# 9_VO_Interface_1.net
KiCad netlist of a schematic drawn in Altium Designer
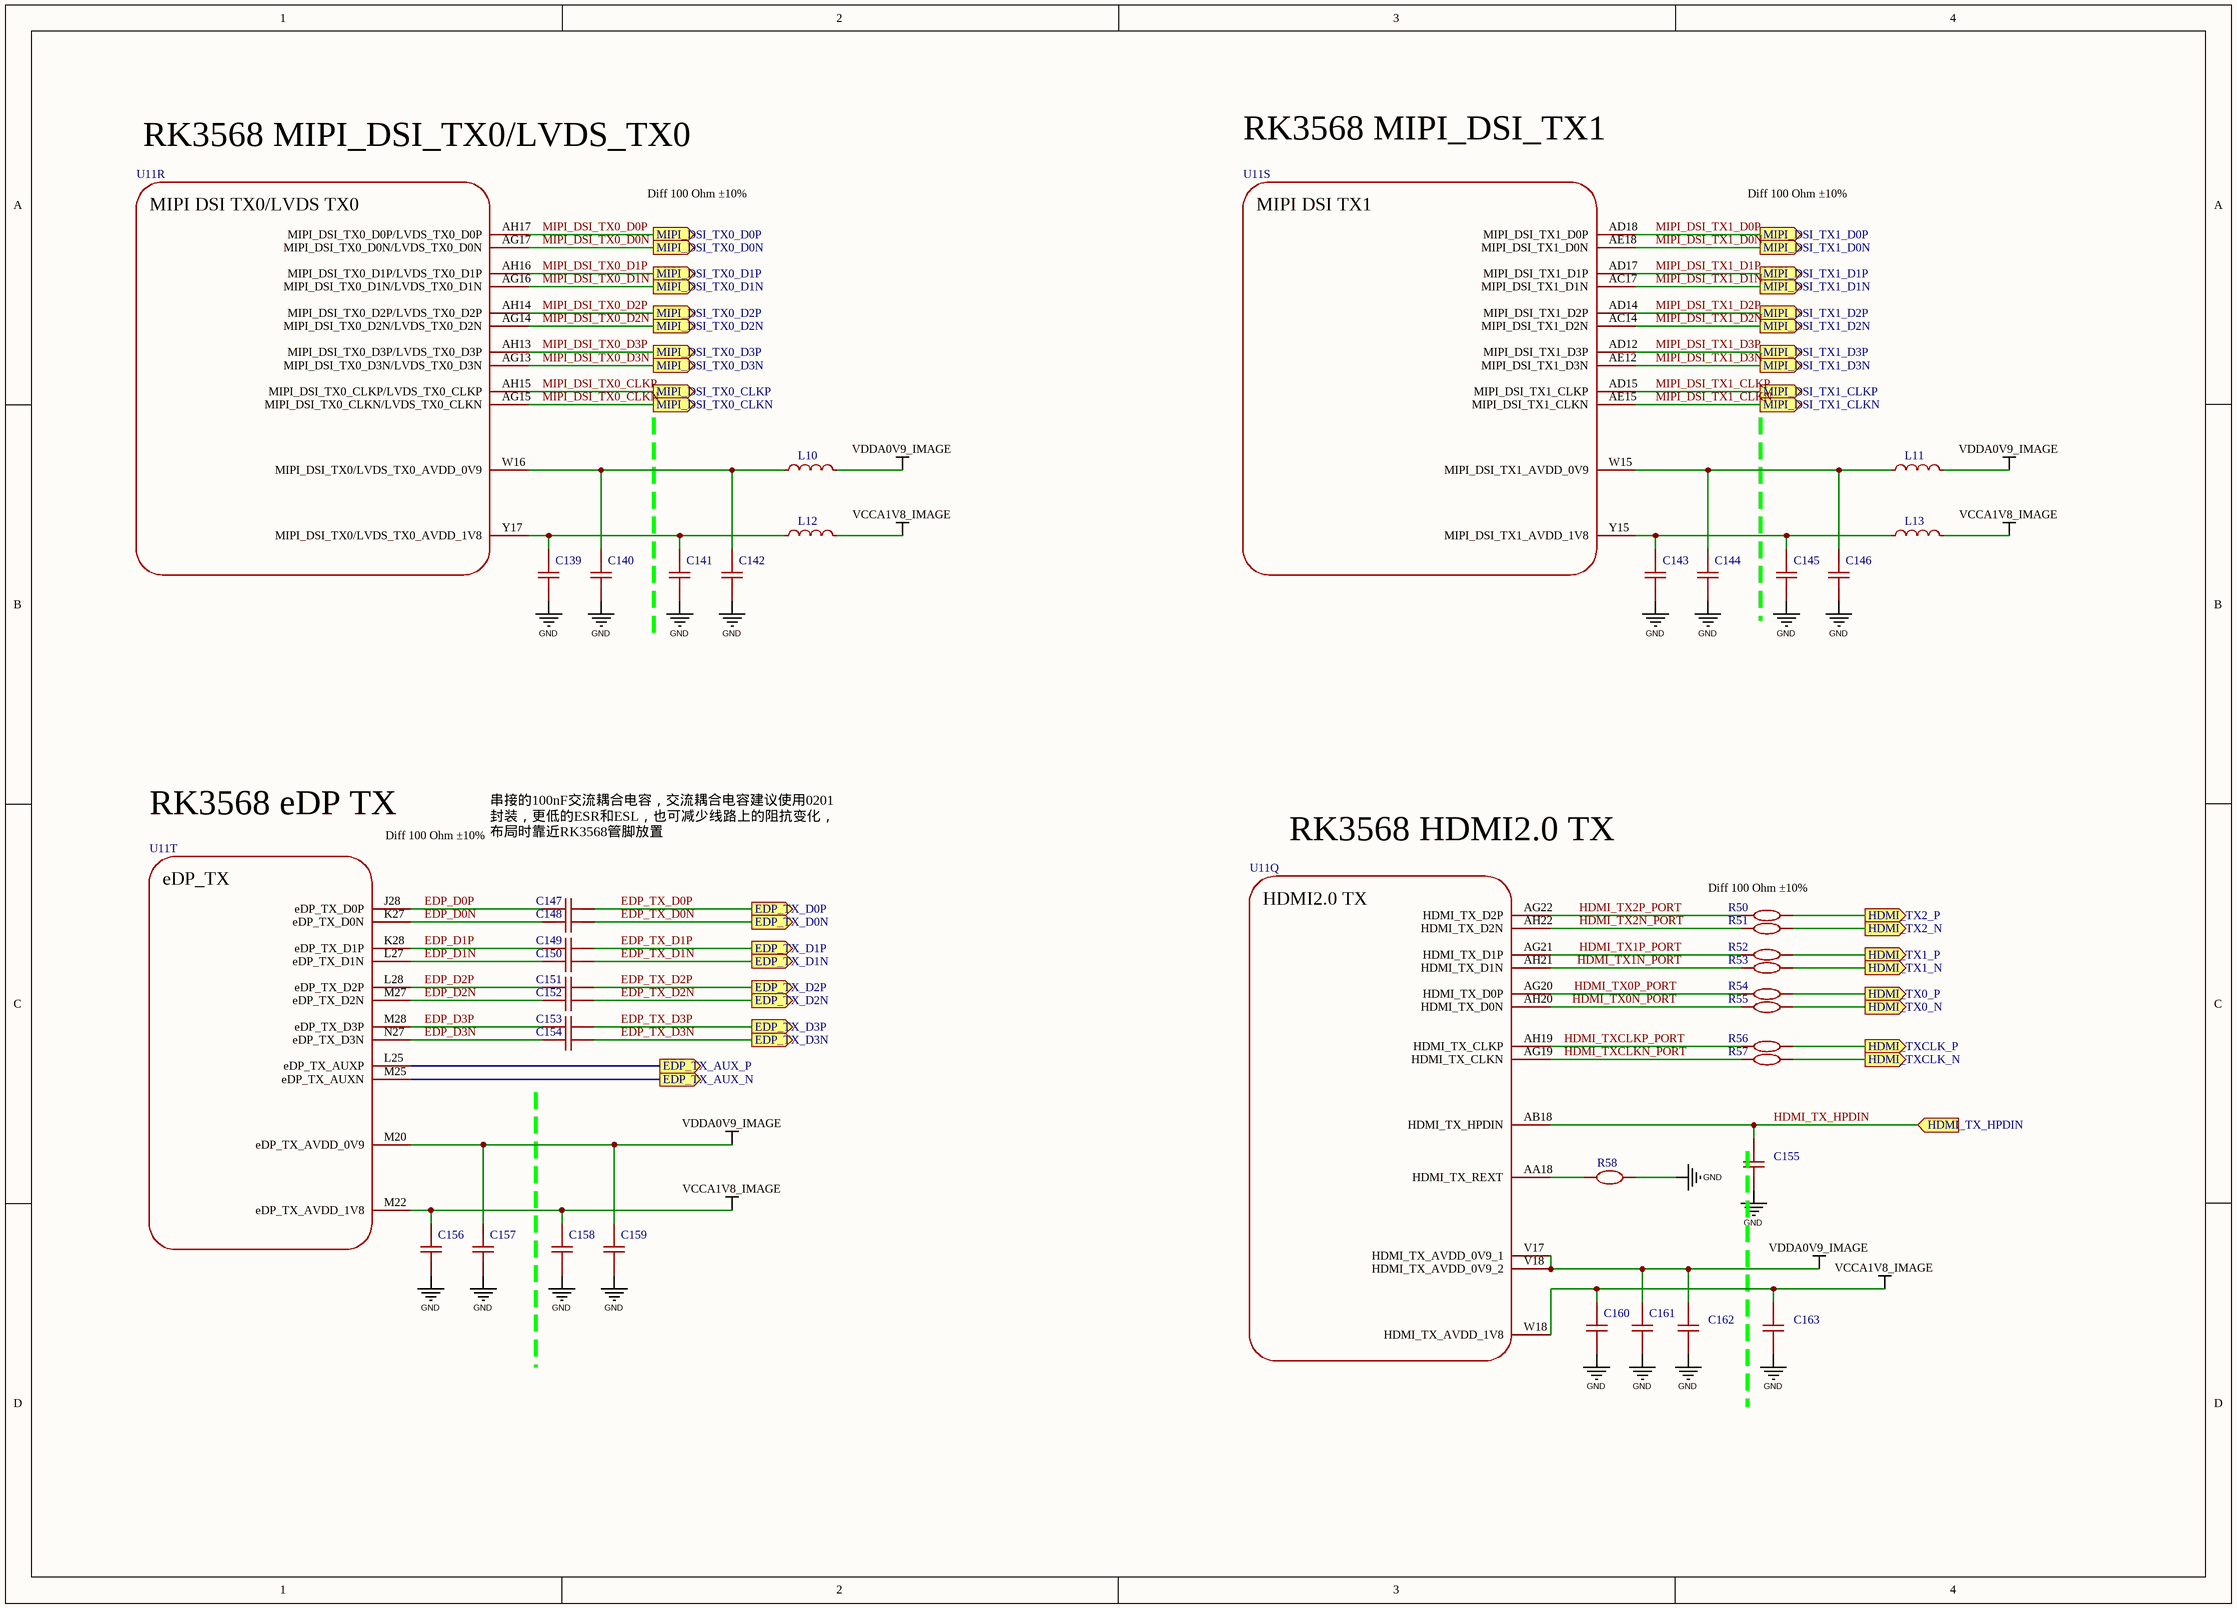
[diagram p0: 9_VO Interface_1.schdoc]

(export (version "E")
  (design (tool "Eeschema 10.0.6"))
  (components
    (comp (ref "C139")
      (value "100nF")
      (footprint "C0201")
      (description "容值:100nF;精度:±10%;额定电压:16V;材质(温度系数):X5R;")
      (fields
        (field (name "MANUFACTURER") "SAMSUNG(三星)")
        (field (name "MANUFACTURER PART") "CL03A104KO3NNNC")
      )
      (libsource (lib "altium-import") (part "root_0_CL03A104KO3NNNC_"))
    )
    (comp (ref "C140")
      (value "100nF")
      (footprint "C0201")
      (description "容值:100nF;精度:±10%;额定电压:16V;材质(温度系数):X5R;")
      (fields
        (field (name "MANUFACTURER") "SAMSUNG(三星)")
        (field (name "MANUFACTURER PART") "CL03A104KO3NNNC")
      )
      (libsource (lib "altium-import") (part "root_0_CL03A104KO3NNNC_"))
    )
    (comp (ref "C141")
      (value "1uF")
      (footprint "C0402")
      (description "容值:1uF;精度:±10%;额定电压:25V;材质(温度系数):X5R;")
      (fields
        (field (name "MANUFACTURER") "SAMSUNG(三星)")
        (field (name "MANUFACTURER PART") "CL05A105KA5NQNC")
      )
      (libsource (lib "altium-import") (part "root_1_CL05A105KA5NQNC_"))
    )
    (comp (ref "C142")
      (value "1uF")
      (footprint "C0402")
      (description "容值:1uF;精度:±10%;额定电压:25V;材质(温度系数):X5R;")
      (fields
        (field (name "MANUFACTURER") "SAMSUNG(三星)")
        (field (name "MANUFACTURER PART") "CL05A105KA5NQNC")
      )
      (libsource (lib "altium-import") (part "root_1_CL05A105KA5NQNC_"))
    )
    (comp (ref "C143")
      (value "100nF")
      (footprint "C0201")
      (description "容值:100nF;精度:±10%;额定电压:16V;材质(温度系数):X5R;")
      (fields
        (field (name "MANUFACTURER") "SAMSUNG(三星)")
        (field (name "MANUFACTURER PART") "CL03A104KO3NNNC")
      )
      (libsource (lib "altium-import") (part "root_0_CL03A104KO3NNNC_"))
    )
    (comp (ref "C144")
      (value "100nF")
      (footprint "C0201")
      (description "容值:100nF;精度:±10%;额定电压:16V;材质(温度系数):X5R;")
      (fields
        (field (name "MANUFACTURER") "SAMSUNG(三星)")
        (field (name "MANUFACTURER PART") "CL03A104KO3NNNC")
      )
      (libsource (lib "altium-import") (part "root_0_CL03A104KO3NNNC_"))
    )
    (comp (ref "C145")
      (value "1uF")
      (footprint "C0402")
      (description "容值:1uF;精度:±10%;额定电压:25V;材质(温度系数):X5R;")
      (fields
        (field (name "MANUFACTURER") "SAMSUNG(三星)")
        (field (name "MANUFACTURER PART") "CL05A105KA5NQNC")
      )
      (libsource (lib "altium-import") (part "root_1_CL05A105KA5NQNC_"))
    )
    (comp (ref "C146")
      (value "1uF")
      (footprint "C0402")
      (description "容值:1uF;精度:±10%;额定电压:25V;材质(温度系数):X5R;")
      (fields
        (field (name "MANUFACTURER") "SAMSUNG(三星)")
        (field (name "MANUFACTURER PART") "CL05A105KA5NQNC")
      )
      (libsource (lib "altium-import") (part "root_1_CL05A105KA5NQNC_"))
    )
    (comp (ref "C147")
      (value "100nF")
      (footprint "C0201")
      (description "容值:100nF;精度:±10%;额定电压:16V;材质(温度系数):X5R;")
      (fields
        (field (name "MANUFACTURER") "SAMSUNG(三星)")
        (field (name "MANUFACTURER PART") "CL03A104KO3NNNC")
      )
      (libsource (lib "altium-import") (part "root_1_CL03A104KO3NNNC_"))
    )
    (comp (ref "C148")
      (value "100nF")
      (footprint "C0201")
      (description "容值:100nF;精度:±10%;额定电压:16V;材质(温度系数):X5R;")
      (fields
        (field (name "MANUFACTURER") "SAMSUNG(三星)")
        (field (name "MANUFACTURER PART") "CL03A104KO3NNNC")
      )
      (libsource (lib "altium-import") (part "root_3_CL03A104KO3NNNC_"))
    )
    (comp (ref "C149")
      (value "100nF")
      (footprint "C0201")
      (description "容值:100nF;精度:±10%;额定电压:16V;材质(温度系数):X5R;")
      (fields
        (field (name "MANUFACTURER") "SAMSUNG(三星)")
        (field (name "MANUFACTURER PART") "CL03A104KO3NNNC")
      )
      (libsource (lib "altium-import") (part "root_1_CL03A104KO3NNNC_"))
    )
    (comp (ref "C150")
      (value "100nF")
      (footprint "C0201")
      (description "容值:100nF;精度:±10%;额定电压:16V;材质(温度系数):X5R;")
      (fields
        (field (name "MANUFACTURER") "SAMSUNG(三星)")
        (field (name "MANUFACTURER PART") "CL03A104KO3NNNC")
      )
      (libsource (lib "altium-import") (part "root_3_CL03A104KO3NNNC_"))
    )
    (comp (ref "C151")
      (value "100nF")
      (footprint "C0201")
      (description "容值:100nF;精度:±10%;额定电压:16V;材质(温度系数):X5R;")
      (fields
        (field (name "MANUFACTURER") "SAMSUNG(三星)")
        (field (name "MANUFACTURER PART") "CL03A104KO3NNNC")
      )
      (libsource (lib "altium-import") (part "root_1_CL03A104KO3NNNC_"))
    )
    (comp (ref "C152")
      (value "100nF")
      (footprint "C0201")
      (description "容值:100nF;精度:±10%;额定电压:16V;材质(温度系数):X5R;")
      (fields
        (field (name "MANUFACTURER") "SAMSUNG(三星)")
        (field (name "MANUFACTURER PART") "CL03A104KO3NNNC")
      )
      (libsource (lib "altium-import") (part "root_3_CL03A104KO3NNNC_"))
    )
    (comp (ref "C153")
      (value "100nF")
      (footprint "C0201")
      (description "容值:100nF;精度:±10%;额定电压:16V;材质(温度系数):X5R;")
      (fields
        (field (name "MANUFACTURER") "SAMSUNG(三星)")
        (field (name "MANUFACTURER PART") "CL03A104KO3NNNC")
      )
      (libsource (lib "altium-import") (part "root_1_CL03A104KO3NNNC_"))
    )
    (comp (ref "C154")
      (value "100nF")
      (footprint "C0201")
      (description "容值:100nF;精度:±10%;额定电压:16V;材质(温度系数):X5R;")
      (fields
        (field (name "MANUFACTURER") "SAMSUNG(三星)")
        (field (name "MANUFACTURER PART") "CL03A104KO3NNNC")
      )
      (libsource (lib "altium-import") (part "root_3_CL03A104KO3NNNC_"))
    )
    (comp (ref "C155")
      (value "100nF")
      (footprint "C0402")
      (description "容值:100nF;精度:±10%;额定电压:50V;材质(温度系数):X7R;")
      (fields
        (field (name "MANUFACTURER") "SAMSUNG(三星)")
        (field (name "MANUFACTURER PART") "CL05B104KB54PNC")
      )
      (libsource (lib "altium-import") (part "root_1_CL05B104KB54PNC_"))
    )
    (comp (ref "C156")
      (value "100nF")
      (footprint "C0201")
      (description "容值:100nF;精度:±10%;额定电压:16V;材质(温度系数):X5R;")
      (fields
        (field (name "MANUFACTURER") "SAMSUNG(三星)")
        (field (name "MANUFACTURER PART") "CL03A104KO3NNNC")
      )
      (libsource (lib "altium-import") (part "root_0_CL03A104KO3NNNC_"))
    )
    (comp (ref "C157")
      (value "100nF")
      (footprint "C0201")
      (description "容值:100nF;精度:±10%;额定电压:16V;材质(温度系数):X5R;")
      (fields
        (field (name "MANUFACTURER") "SAMSUNG(三星)")
        (field (name "MANUFACTURER PART") "CL03A104KO3NNNC")
      )
      (libsource (lib "altium-import") (part "root_0_CL03A104KO3NNNC_"))
    )
    (comp (ref "C158")
      (value "1uF")
      (footprint "C0402")
      (description "容值:1uF;精度:±10%;额定电压:25V;材质(温度系数):X5R;")
      (fields
        (field (name "MANUFACTURER") "SAMSUNG(三星)")
        (field (name "MANUFACTURER PART") "CL05A105KA5NQNC")
      )
      (libsource (lib "altium-import") (part "root_1_CL05A105KA5NQNC_"))
    )
    (comp (ref "C159")
      (value "1uF")
      (footprint "C0402")
      (description "容值:1uF;精度:±10%;额定电压:25V;材质(温度系数):X5R;")
      (fields
        (field (name "MANUFACTURER") "SAMSUNG(三星)")
        (field (name "MANUFACTURER PART") "CL05A105KA5NQNC")
      )
      (libsource (lib "altium-import") (part "root_1_CL05A105KA5NQNC_"))
    )
    (comp (ref "C160")
      (value "100nF")
      (footprint "C0201")
      (description "容值:100nF;精度:±10%;额定电压:16V;材质(温度系数):X5R;")
      (fields
        (field (name "MANUFACTURER") "SAMSUNG(三星)")
        (field (name "MANUFACTURER PART") "CL03A104KO3NNNC")
      )
      (libsource (lib "altium-import") (part "root_0_CL03A104KO3NNNC_"))
    )
    (comp (ref "C161")
      (value "100nF")
      (footprint "C0201")
      (description "容值:100nF;精度:±10%;额定电压:16V;材质(温度系数):X5R;")
      (fields
        (field (name "MANUFACTURER") "SAMSUNG(三星)")
        (field (name "MANUFACTURER PART") "CL03A104KO3NNNC")
      )
      (libsource (lib "altium-import") (part "root_0_CL03A104KO3NNNC_"))
    )
    (comp (ref "C162")
      (value "4.7uF")
      (footprint "C0201")
      (description "容值:4.7uF;精度:±20%;额定电压:6.3V;材质(温度系数):X5R;")
      (fields
        (field (name "MANUFACTURER") "muRata(村田)")
        (field (name "MANUFACTURER PART") "GRM035R60J475ME15D")
      )
      (libsource (lib "altium-import") (part "root_2_GRM035R60J475ME15D_"))
    )
    (comp (ref "C163")
      (value "4.7uF")
      (footprint "C0201")
      (description "容值:4.7uF;精度:±20%;额定电压:6.3V;材质(温度系数):X5R;")
      (fields
        (field (name "MANUFACTURER") "muRata(村田)")
        (field (name "MANUFACTURER PART") "GRM035R60J475ME15D")
      )
      (libsource (lib "altium-import") (part "root_2_GRM035R60J475ME15D_"))
    )
    (comp (ref "L10")
      (value "120R 100MHz")
      (footprint "L0603")
      (description "标称阻抗@测试频率:120Ω@100MHz;误差:±25%;直流电阻(RDC):50mΩ;")
      (fields (field (name "MANUFACTURER") "muRata(村田)") (field (name "TOLERANCE") "±25%"))
      (libsource (lib "altium-import") (part "root_0_BLM18PG121SN1D_"))
    )
    (comp (ref "L11")
      (value "120R 100MHz")
      (footprint "L0603")
      (description "标称阻抗@测试频率:120Ω@100MHz;误差:±25%;直流电阻(RDC):50mΩ;")
      (fields (field (name "MANUFACTURER") "muRata(村田)") (field (name "TOLERANCE") "±25%"))
      (libsource (lib "altium-import") (part "root_0_BLM18PG121SN1D_"))
    )
    (comp (ref "L12")
      (value "120R 100MHz")
      (footprint "L0603")
      (description "标称阻抗@测试频率:120Ω@100MHz;误差:±25%;直流电阻(RDC):50mΩ;")
      (fields (field (name "MANUFACTURER") "muRata(村田)") (field (name "TOLERANCE") "±25%"))
      (libsource (lib "altium-import") (part "root_0_BLM18PG121SN1D_"))
    )
    (comp (ref "L13")
      (value "120R 100MHz")
      (footprint "L0603")
      (description "标称阻抗@测试频率:120Ω@100MHz;误差:±25%;直流电阻(RDC):50mΩ;")
      (fields (field (name "MANUFACTURER") "muRata(村田)") (field (name "TOLERANCE") "±25%"))
      (libsource (lib "altium-import") (part "root_0_BLM18PG121SN1D_"))
    )
    (comp (ref "R50")
      (value "2.2Ω")
      (footprint "R0201")
      (description "电阻类型:厚膜电阻;阻值:2.2Ω;精度:±5%;功率:50mW;最大工作电压:25V;温度系数:±400ppm/℃;")
      (fields
        (field (name "MANUFACTURER") "UNI-ROYAL(厚声)")
        (field (name "MANUFACTURER PART") "0201WMJ022JTEE")
      )
      (libsource (lib "altium-import") (part "root_0_0201WMJ022JTEE_"))
    )
    (comp (ref "R51")
      (value "2.2Ω")
      (footprint "R0201")
      (description "电阻类型:厚膜电阻;阻值:2.2Ω;精度:±5%;功率:50mW;最大工作电压:25V;温度系数:±400ppm/℃;")
      (fields
        (field (name "MANUFACTURER") "UNI-ROYAL(厚声)")
        (field (name "MANUFACTURER PART") "0201WMJ022JTEE")
      )
      (libsource (lib "altium-import") (part "root_0_0201WMJ022JTEE_"))
    )
    (comp (ref "R52")
      (value "2.2Ω")
      (footprint "R0201")
      (description "电阻类型:厚膜电阻;阻值:2.2Ω;精度:±5%;功率:50mW;最大工作电压:25V;温度系数:±400ppm/℃;")
      (fields
        (field (name "MANUFACTURER") "UNI-ROYAL(厚声)")
        (field (name "MANUFACTURER PART") "0201WMJ022JTEE")
      )
      (libsource (lib "altium-import") (part "root_0_0201WMJ022JTEE_"))
    )
    (comp (ref "R53")
      (value "2.2Ω")
      (footprint "R0201")
      (description "电阻类型:厚膜电阻;阻值:2.2Ω;精度:±5%;功率:50mW;最大工作电压:25V;温度系数:±400ppm/℃;")
      (fields
        (field (name "MANUFACTURER") "UNI-ROYAL(厚声)")
        (field (name "MANUFACTURER PART") "0201WMJ022JTEE")
      )
      (libsource (lib "altium-import") (part "root_0_0201WMJ022JTEE_"))
    )
    (comp (ref "R54")
      (value "2.2Ω")
      (footprint "R0201")
      (description "电阻类型:厚膜电阻;阻值:2.2Ω;精度:±5%;功率:50mW;最大工作电压:25V;温度系数:±400ppm/℃;")
      (fields
        (field (name "MANUFACTURER") "UNI-ROYAL(厚声)")
        (field (name "MANUFACTURER PART") "0201WMJ022JTEE")
      )
      (libsource (lib "altium-import") (part "root_0_0201WMJ022JTEE_"))
    )
    (comp (ref "R55")
      (value "2.2Ω")
      (footprint "R0201")
      (description "电阻类型:厚膜电阻;阻值:2.2Ω;精度:±5%;功率:50mW;最大工作电压:25V;温度系数:±400ppm/℃;")
      (fields
        (field (name "MANUFACTURER") "UNI-ROYAL(厚声)")
        (field (name "MANUFACTURER PART") "0201WMJ022JTEE")
      )
      (libsource (lib "altium-import") (part "root_0_0201WMJ022JTEE_"))
    )
    (comp (ref "R56")
      (value "2.2Ω")
      (footprint "R0201")
      (description "电阻类型:厚膜电阻;阻值:2.2Ω;精度:±5%;功率:50mW;最大工作电压:25V;温度系数:±400ppm/℃;")
      (fields
        (field (name "MANUFACTURER") "UNI-ROYAL(厚声)")
        (field (name "MANUFACTURER PART") "0201WMJ022JTEE")
      )
      (libsource (lib "altium-import") (part "root_0_0201WMJ022JTEE_"))
    )
    (comp (ref "R57")
      (value "2.2Ω")
      (footprint "R0201")
      (description "电阻类型:厚膜电阻;阻值:2.2Ω;精度:±5%;功率:50mW;最大工作电压:25V;温度系数:±400ppm/℃;")
      (fields
        (field (name "MANUFACTURER") "UNI-ROYAL(厚声)")
        (field (name "MANUFACTURER PART") "0201WMJ022JTEE")
      )
      (libsource (lib "altium-import") (part "root_0_0201WMJ022JTEE_"))
    )
    (comp (ref "R58")
      (value "1.62kΩ")
      (footprint "R0201")
      (description "电阻类型:厚膜电阻;阻值:1.62kΩ;精度:±1%;功率:50mW;最大工作电压:25V;温度系数:±200ppm/℃;")
      (fields
        (field (name "MANUFACTURER") "UNI-ROYAL(厚声)")
        (field (name "MANUFACTURER PART") "0201WMF1621TEE")
      )
      (libsource (lib "altium-import") (part "root_0_0201WMF1621TEE_"))
    )
    (comp (ref "U11")
      (value "SOC_RK3568")
      (footprint "RK3568")
      (fields (field (name "MANUFACTURER") "Rockchip (瑞芯微)") (field (name "CREATED BY") "JJJ"))
      (libsource (lib "altium-import") (part "root_0_SOC_RK3568_"))
    )
  )
  (nets
    (net (code "1") (name "/EDP_D0N") (class "Default")
      (node (ref "C148") (pin "1") (pinfunction "1_1") (pintype "passive"))
      (node (ref "U11") (pin "K27") (pinfunction "eDP_TX_D0N_K27") (pintype "passive"))
    )
    (net (code "2") (name "/EDP_D0P") (class "Default")
      (node (ref "C147") (pin "2") (pinfunction "2_2") (pintype "passive"))
      (node (ref "U11") (pin "J28") (pinfunction "eDP_TX_D0P_J28") (pintype "passive"))
    )
    (net (code "3") (name "/EDP_D1N") (class "Default")
      (node (ref "C150") (pin "1") (pinfunction "1_1") (pintype "passive"))
      (node (ref "U11") (pin "L27") (pinfunction "eDP_TX_D1N_L27") (pintype "passive"))
    )
    (net (code "4") (name "/EDP_D1P") (class "Default")
      (node (ref "C149") (pin "2") (pinfunction "2_2") (pintype "passive"))
      (node (ref "U11") (pin "K28") (pinfunction "eDP_TX_D1P_K28") (pintype "passive"))
    )
    (net (code "5") (name "/EDP_D2N") (class "Default")
      (node (ref "C152") (pin "1") (pinfunction "1_1") (pintype "passive"))
      (node (ref "U11") (pin "M27") (pinfunction "eDP_TX_D2N_M27") (pintype "passive"))
    )
    (net (code "6") (name "/EDP_D2P") (class "Default")
      (node (ref "C151") (pin "2") (pinfunction "2_2") (pintype "passive"))
      (node (ref "U11") (pin "L28") (pinfunction "eDP_TX_D2P_L28") (pintype "passive"))
    )
    (net (code "7") (name "/EDP_D3N") (class "Default")
      (node (ref "C154") (pin "1") (pinfunction "1_1") (pintype "passive"))
      (node (ref "U11") (pin "N27") (pinfunction "eDP_TX_D3N_N27") (pintype "passive"))
    )
    (net (code "8") (name "/EDP_D3P") (class "Default")
      (node (ref "C153") (pin "2") (pinfunction "2_2") (pintype "passive"))
      (node (ref "U11") (pin "M28") (pinfunction "eDP_TX_D3P_M28") (pintype "passive"))
    )
    (net (code "9") (name "/EDP_TX_AUX_N") (class "Default")
      (node (ref "U11") (pin "M25") (pinfunction "eDP_TX_AUXN_M25") (pintype "passive"))
    )
    (net (code "10") (name "/EDP_TX_AUX_P") (class "Default")
      (node (ref "U11") (pin "L25") (pinfunction "eDP_TX_AUXP_L25") (pintype "passive"))
    )
    (net (code "11") (name "/EDP_TX_D0N") (class "Default")
      (node (ref "C148") (pin "2") (pinfunction "2_2") (pintype "passive"))
    )
    (net (code "12") (name "/EDP_TX_D0P") (class "Default")
      (node (ref "C147") (pin "1") (pinfunction "1_1") (pintype "passive"))
    )
    (net (code "13") (name "/EDP_TX_D1N") (class "Default")
      (node (ref "C150") (pin "2") (pinfunction "2_2") (pintype "passive"))
    )
    (net (code "14") (name "/EDP_TX_D1P") (class "Default")
      (node (ref "C149") (pin "1") (pinfunction "1_1") (pintype "passive"))
    )
    (net (code "15") (name "/EDP_TX_D2N") (class "Default")
      (node (ref "C152") (pin "2") (pinfunction "2_2") (pintype "passive"))
    )
    (net (code "16") (name "/EDP_TX_D2P") (class "Default")
      (node (ref "C151") (pin "1") (pinfunction "1_1") (pintype "passive"))
    )
    (net (code "17") (name "/EDP_TX_D3N") (class "Default")
      (node (ref "C154") (pin "2") (pinfunction "2_2") (pintype "passive"))
    )
    (net (code "18") (name "/EDP_TX_D3P") (class "Default")
      (node (ref "C153") (pin "1") (pinfunction "1_1") (pintype "passive"))
    )
    (net (code "19") (name "/HDMI_TX0N_PORT") (class "Default")
      (node (ref "R55") (pin "1") (pinfunction "1_1") (pintype "passive"))
      (node (ref "U11") (pin "AH20") (pinfunction "HDMI_TX_D0N_AH20") (pintype "passive"))
    )
    (net (code "20") (name "/HDMI_TX0P_PORT") (class "Default")
      (node (ref "R54") (pin "1") (pinfunction "1_1") (pintype "passive"))
      (node (ref "U11") (pin "AG20") (pinfunction "HDMI_TX_D0P_AG20") (pintype "passive"))
    )
    (net (code "21") (name "/HDMI_TX0_N") (class "Default")
      (node (ref "R55") (pin "2") (pinfunction "2_2") (pintype "passive"))
    )
    (net (code "22") (name "/HDMI_TX0_P") (class "Default")
      (node (ref "R54") (pin "2") (pinfunction "2_2") (pintype "passive"))
    )
    (net (code "23") (name "/HDMI_TX1N_PORT") (class "Default")
      (node (ref "R53") (pin "1") (pinfunction "1_1") (pintype "passive"))
      (node (ref "U11") (pin "AH21") (pinfunction "HDMI_TX_D1N_AH21") (pintype "passive"))
    )
    (net (code "24") (name "/HDMI_TX1P_PORT") (class "Default")
      (node (ref "R52") (pin "1") (pinfunction "1_1") (pintype "passive"))
      (node (ref "U11") (pin "AG21") (pinfunction "HDMI_TX_D1P_AG21") (pintype "passive"))
    )
    (net (code "25") (name "/HDMI_TX1_N") (class "Default")
      (node (ref "R53") (pin "2") (pinfunction "2_2") (pintype "passive"))
    )
    (net (code "26") (name "/HDMI_TX1_P") (class "Default")
      (node (ref "R52") (pin "2") (pinfunction "2_2") (pintype "passive"))
    )
    (net (code "27") (name "/HDMI_TX2N_PORT") (class "Default")
      (node (ref "R51") (pin "1") (pinfunction "1_1") (pintype "passive"))
      (node (ref "U11") (pin "AH22") (pinfunction "HDMI_TX_D2N_AH22") (pintype "passive"))
    )
    (net (code "28") (name "/HDMI_TX2P_PORT") (class "Default")
      (node (ref "R50") (pin "1") (pinfunction "1_1") (pintype "passive"))
      (node (ref "U11") (pin "AG22") (pinfunction "HDMI_TX_D2P_AG22") (pintype "passive"))
    )
    (net (code "29") (name "/HDMI_TX2_N") (class "Default")
      (node (ref "R51") (pin "2") (pinfunction "2_2") (pintype "passive"))
    )
    (net (code "30") (name "/HDMI_TX2_P") (class "Default")
      (node (ref "R50") (pin "2") (pinfunction "2_2") (pintype "passive"))
    )
    (net (code "31") (name "/HDMI_TXCLKN_PORT") (class "Default")
      (node (ref "R57") (pin "1") (pinfunction "1_1") (pintype "passive"))
      (node (ref "U11") (pin "AG19") (pinfunction "HDMI_TX_CLKN_AG19") (pintype "passive"))
    )
    (net (code "32") (name "/HDMI_TXCLKP_PORT") (class "Default")
      (node (ref "R56") (pin "1") (pinfunction "1_1") (pintype "passive"))
      (node (ref "U11") (pin "AH19") (pinfunction "HDMI_TX_CLKP_AH19") (pintype "passive"))
    )
    (net (code "33") (name "/HDMI_TXCLK_N") (class "Default")
      (node (ref "R57") (pin "2") (pinfunction "2_2") (pintype "passive"))
    )
    (net (code "34") (name "/HDMI_TXCLK_P") (class "Default")
      (node (ref "R56") (pin "2") (pinfunction "2_2") (pintype "passive"))
    )
    (net (code "35") (name "/HDMI_TX_HPDIN") (class "Default")
      (node (ref "C155") (pin "2") (pinfunction "2_2") (pintype "passive"))
      (node (ref "U11") (pin "AB18") (pinfunction "HDMI_TX_HPDIN_AB18") (pintype "passive"))
    )
    (net (code "36") (name "/MIPI_DSI_TX0_CLKN") (class "Default")
      (node (ref "U11") (pin "AG15") (pinfunction "MIPI_DSI_TX0_CLKN/LVDS_TX0_CLKN_AG15") (pintype "passive"))
    )
    (net (code "37") (name "/MIPI_DSI_TX0_CLKP") (class "Default")
      (node (ref "U11") (pin "AH15") (pinfunction "MIPI_DSI_TX0_CLKP/LVDS_TX0_CLKP_AH15") (pintype "passive"))
    )
    (net (code "38") (name "/MIPI_DSI_TX0_D0N") (class "Default")
      (node (ref "U11") (pin "AG17") (pinfunction "MIPI_DSI_TX0_D0N/LVDS_TX0_D0N_AG17") (pintype "passive"))
    )
    (net (code "39") (name "/MIPI_DSI_TX0_D0P") (class "Default")
      (node (ref "U11") (pin "AH17") (pinfunction "MIPI_DSI_TX0_D0P/LVDS_TX0_D0P_AH17") (pintype "passive"))
    )
    (net (code "40") (name "/MIPI_DSI_TX0_D1N") (class "Default")
      (node (ref "U11") (pin "AG16") (pinfunction "MIPI_DSI_TX0_D1N/LVDS_TX0_D1N_AG16") (pintype "passive"))
    )
    (net (code "41") (name "/MIPI_DSI_TX0_D1P") (class "Default")
      (node (ref "U11") (pin "AH16") (pinfunction "MIPI_DSI_TX0_D1P/LVDS_TX0_D1P_AH16") (pintype "passive"))
    )
    (net (code "42") (name "/MIPI_DSI_TX0_D2N") (class "Default")
      (node (ref "U11") (pin "AG14") (pinfunction "MIPI_DSI_TX0_D2N/LVDS_TX0_D2N_AG14") (pintype "passive"))
    )
    (net (code "43") (name "/MIPI_DSI_TX0_D2P") (class "Default")
      (node (ref "U11") (pin "AH14") (pinfunction "MIPI_DSI_TX0_D2P/LVDS_TX0_D2P_AH14") (pintype "passive"))
    )
    (net (code "44") (name "/MIPI_DSI_TX0_D3N") (class "Default")
      (node (ref "U11") (pin "AG13") (pinfunction "MIPI_DSI_TX0_D3N/LVDS_TX0_D3N_AG13") (pintype "passive"))
    )
    (net (code "45") (name "/MIPI_DSI_TX0_D3P") (class "Default")
      (node (ref "U11") (pin "AH13") (pinfunction "MIPI_DSI_TX0_D3P/LVDS_TX0_D3P_AH13") (pintype "passive"))
    )
    (net (code "46") (name "/MIPI_DSI_TX1_CLKN") (class "Default")
      (node (ref "U11") (pin "AE15") (pinfunction "MIPI_DSI_TX1_CLKN_AE15") (pintype "passive"))
    )
    (net (code "47") (name "/MIPI_DSI_TX1_CLKP") (class "Default")
      (node (ref "U11") (pin "AD15") (pinfunction "MIPI_DSI_TX1_CLKP_AD15") (pintype "passive"))
    )
    (net (code "48") (name "/MIPI_DSI_TX1_D0N") (class "Default")
      (node (ref "U11") (pin "AE18") (pinfunction "MIPI_DSI_TX1_D0N_AE18") (pintype "passive"))
    )
    (net (code "49") (name "/MIPI_DSI_TX1_D0P") (class "Default")
      (node (ref "U11") (pin "AD18") (pinfunction "MIPI_DSI_TX1_D0P_AD18") (pintype "passive"))
    )
    (net (code "50") (name "/MIPI_DSI_TX1_D1N") (class "Default")
      (node (ref "U11") (pin "AC17") (pinfunction "MIPI_DSI_TX1_D1N_AC17") (pintype "passive"))
    )
    (net (code "51") (name "/MIPI_DSI_TX1_D1P") (class "Default")
      (node (ref "U11") (pin "AD17") (pinfunction "MIPI_DSI_TX1_D1P_AD17") (pintype "passive"))
    )
    (net (code "52") (name "/MIPI_DSI_TX1_D2N") (class "Default")
      (node (ref "U11") (pin "AC14") (pinfunction "MIPI_DSI_TX1_D2N_AC14") (pintype "passive"))
    )
    (net (code "53") (name "/MIPI_DSI_TX1_D2P") (class "Default")
      (node (ref "U11") (pin "AD14") (pinfunction "MIPI_DSI_TX1_D2P_AD14") (pintype "passive"))
    )
    (net (code "54") (name "/MIPI_DSI_TX1_D3N") (class "Default")
      (node (ref "U11") (pin "AE12") (pinfunction "MIPI_DSI_TX1_D3N_AE12") (pintype "passive"))
    )
    (net (code "55") (name "/MIPI_DSI_TX1_D3P") (class "Default")
      (node (ref "U11") (pin "AD12") (pinfunction "MIPI_DSI_TX1_D3P_AD12") (pintype "passive"))
    )
    (net (code "56") (name "GND") (class "Default")
      (node (ref "C139") (pin "1") (pinfunction "1_1") (pintype "passive"))
      (node (ref "C140") (pin "1") (pinfunction "1_1") (pintype "passive"))
      (node (ref "C141") (pin "1") (pinfunction "1_1") (pintype "passive"))
      (node (ref "C142") (pin "1") (pinfunction "1_1") (pintype "passive"))
      (node (ref "C143") (pin "1") (pinfunction "1_1") (pintype "passive"))
      (node (ref "C144") (pin "1") (pinfunction "1_1") (pintype "passive"))
      (node (ref "C145") (pin "1") (pinfunction "1_1") (pintype "passive"))
      (node (ref "C146") (pin "1") (pinfunction "1_1") (pintype "passive"))
      (node (ref "C155") (pin "1") (pinfunction "1_1") (pintype "passive"))
      (node (ref "C156") (pin "1") (pinfunction "1_1") (pintype "passive"))
      (node (ref "C157") (pin "1") (pinfunction "1_1") (pintype "passive"))
      (node (ref "C158") (pin "1") (pinfunction "1_1") (pintype "passive"))
      (node (ref "C159") (pin "1") (pinfunction "1_1") (pintype "passive"))
      (node (ref "C160") (pin "1") (pinfunction "1_1") (pintype "passive"))
      (node (ref "C161") (pin "1") (pinfunction "1_1") (pintype "passive"))
      (node (ref "C162") (pin "2") (pinfunction "2_2") (pintype "passive"))
      (node (ref "C163") (pin "2") (pinfunction "2_2") (pintype "passive"))
      (node (ref "R58") (pin "2") (pinfunction "2_2") (pintype "passive"))
    )
    (net (code "57") (name "Net-(U11Q-HDMI_TX_REXT)") (class "Default")
      (node (ref "R58") (pin "1") (pinfunction "1_1") (pintype "passive"))
      (node (ref "U11") (pin "AA18") (pinfunction "HDMI_TX_REXT_AA18") (pintype "passive"))
    )
    (net (code "58") (name "Net-(U11R-MIPI_DSI_TX0{slash}LVDS_TX0_AVDD_0V9)") (class "Default")
      (node (ref "C140") (pin "2") (pinfunction "2_2") (pintype "passive"))
      (node (ref "C142") (pin "2") (pinfunction "2_2") (pintype "passive"))
      (node (ref "L10") (pin "1") (pinfunction "1_1") (pintype "passive"))
      (node (ref "U11") (pin "W16") (pinfunction "MIPI_DSI_TX0/LVDS_TX0_AVDD_0V9_W16") (pintype "passive"))
    )
    (net (code "59") (name "Net-(U11R-MIPI_DSI_TX0{slash}LVDS_TX0_AVDD_1V8)") (class "Default")
      (node (ref "C139") (pin "2") (pinfunction "2_2") (pintype "passive"))
      (node (ref "C141") (pin "2") (pinfunction "2_2") (pintype "passive"))
      (node (ref "L12") (pin "1") (pinfunction "1_1") (pintype "passive"))
      (node (ref "U11") (pin "Y17") (pinfunction "MIPI_DSI_TX0/LVDS_TX0_AVDD_1V8_Y17") (pintype "passive"))
    )
    (net (code "60") (name "Net-(U11S-MIPI_DSI_TX1_AVDD_0V9)") (class "Default")
      (node (ref "C144") (pin "2") (pinfunction "2_2") (pintype "passive"))
      (node (ref "C146") (pin "2") (pinfunction "2_2") (pintype "passive"))
      (node (ref "L11") (pin "1") (pinfunction "1_1") (pintype "passive"))
      (node (ref "U11") (pin "W15") (pinfunction "MIPI_DSI_TX1_AVDD_0V9_W15") (pintype "passive"))
    )
    (net (code "61") (name "Net-(U11S-MIPI_DSI_TX1_AVDD_1V8)") (class "Default")
      (node (ref "C143") (pin "2") (pinfunction "2_2") (pintype "passive"))
      (node (ref "C145") (pin "2") (pinfunction "2_2") (pintype "passive"))
      (node (ref "L13") (pin "1") (pinfunction "1_1") (pintype "passive"))
      (node (ref "U11") (pin "Y15") (pinfunction "MIPI_DSI_TX1_AVDD_1V8_Y15") (pintype "passive"))
    )
    (net (code "62") (name "VCCA1V8_IMAGE") (class "Default")
      (node (ref "C156") (pin "2") (pinfunction "2_2") (pintype "passive"))
      (node (ref "C158") (pin "2") (pinfunction "2_2") (pintype "passive"))
      (node (ref "C160") (pin "2") (pinfunction "2_2") (pintype "passive"))
      (node (ref "C163") (pin "1") (pinfunction "1_1") (pintype "passive"))
      (node (ref "L12") (pin "2") (pinfunction "2_2") (pintype "passive"))
      (node (ref "L13") (pin "2") (pinfunction "2_2") (pintype "passive"))
      (node (ref "U11") (pin "M22") (pinfunction "eDP_TX_AVDD_1V8_M22") (pintype "passive"))
      (node (ref "U11") (pin "W18") (pinfunction "HDMI_TX_AVDD_1V8_W18") (pintype "passive"))
    )
    (net (code "63") (name "VDDA0V9_IMAGE") (class "Default")
      (node (ref "C157") (pin "2") (pinfunction "2_2") (pintype "passive"))
      (node (ref "C159") (pin "2") (pinfunction "2_2") (pintype "passive"))
      (node (ref "C161") (pin "2") (pinfunction "2_2") (pintype "passive"))
      (node (ref "C162") (pin "1") (pinfunction "1_1") (pintype "passive"))
      (node (ref "L10") (pin "2") (pinfunction "2_2") (pintype "passive"))
      (node (ref "L11") (pin "2") (pinfunction "2_2") (pintype "passive"))
      (node (ref "U11") (pin "M20") (pinfunction "eDP_TX_AVDD_0V9_M20") (pintype "passive"))
      (node (ref "U11") (pin "V17") (pinfunction "HDMI_TX_AVDD_0V9_1_V17") (pintype "passive"))
      (node (ref "U11") (pin "V18") (pinfunction "HDMI_TX_AVDD_0V9_2_V18") (pintype "passive"))
    )
  )
)
